# CM_ALIM.net
KiCad netlist of a schematic drawn in Altium Designer
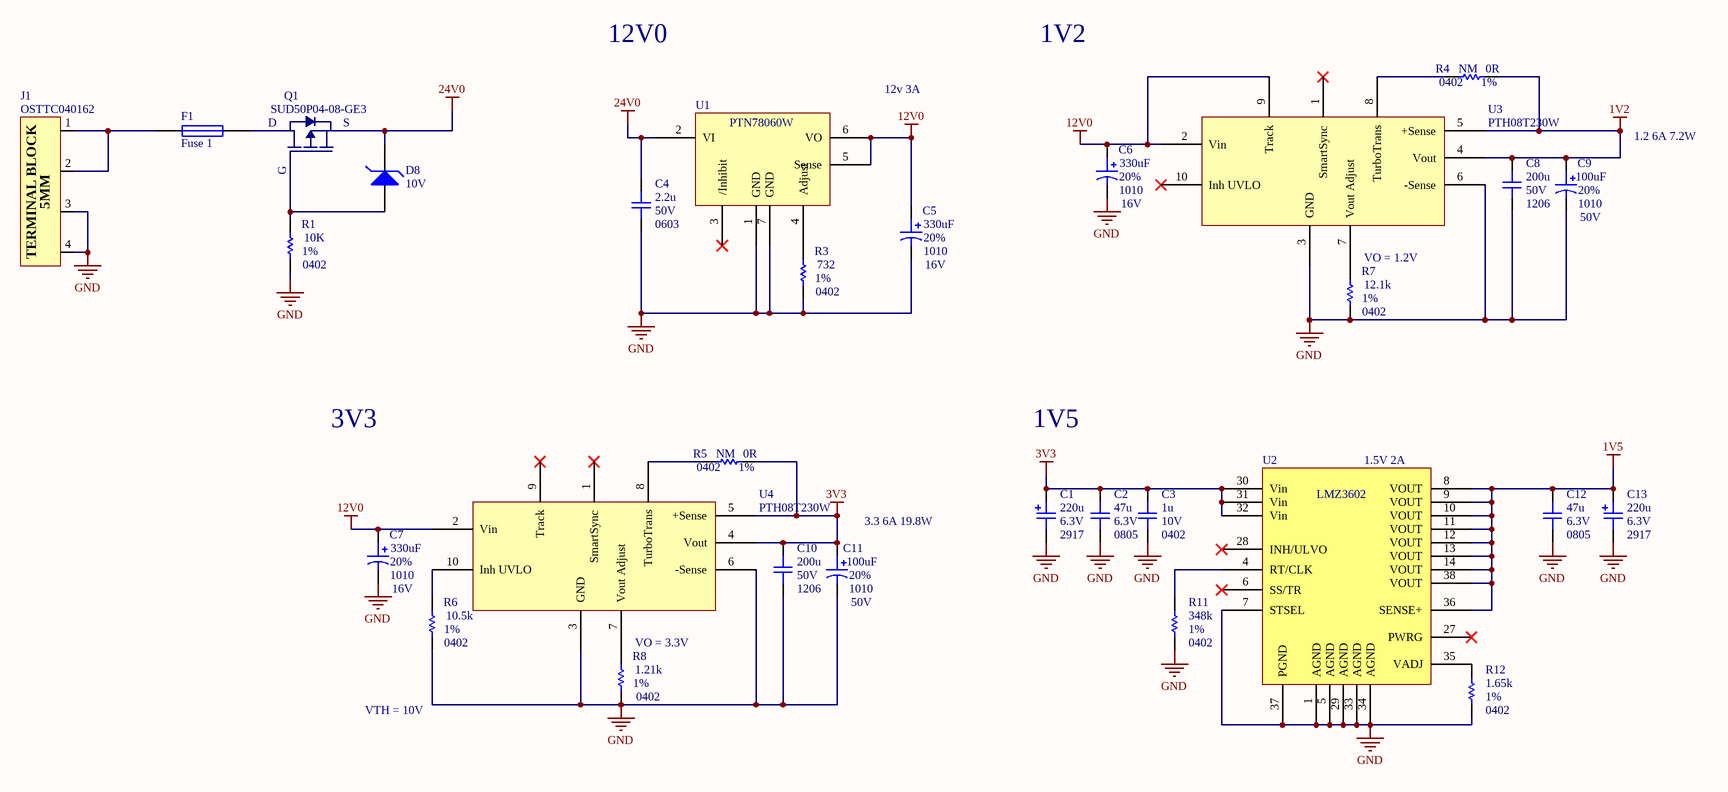
[diagram p0: CM_ALIM.SchDoc]

(export (version "E")
  (design (tool "Eeschema 10.0.6"))
  (components
    (comp (ref "C1")
      (value "220u")
      (footprint "CAP_TAN_2917(D)")
      (description "CAP - TANTALUM - 2917")
      (fields
        (field (name "VOLTAGE") "6.3V")
        (field (name "PACKAGE") "2917")
        (field (name "Comment") "CAP - TANTALUM - CASE D")
        (field (name "CREATEDBY") "Jonathan Bouchard")
      )
      (libsource (lib "S7CAS_Lib2019_REV1_00") (part "CAP_TANT_2917(D)"))
    )
    (comp (ref "C2")
      (value "47u")
      (footprint "CAP_0805")
      (description "CAP - 0805")
      (fields
        (field (name "VOLTAGE") "6.3V")
        (field (name "PACKAGE") "0805")
        (field (name "CREATEDBY") "Jonathan Bouchard")
      )
      (libsource (lib "S7CAS_Lib2019_REV1_00") (part "CAP - 0805"))
    )
    (comp (ref "C3")
      (value "1u")
      (footprint "CAP_0402")
      (description "CAP - 0402")
      (fields
        (field (name "VOLTAGE") "10V")
        (field (name "PACKAGE") "0402")
        (field (name "CREATEDBY") "Jonathan Bouchard")
      )
      (libsource (lib "S7CAS_Lib2019_REV1_00") (part "CAP - 0402"))
    )
    (comp (ref "C4")
      (value "2.2u")
      (footprint "CAP_0603")
      (description "CAP - 0603")
      (fields
        (field (name "VOLTAGE") "50V")
        (field (name "PACKAGE") "0603")
        (field (name "CREATEDBY") "Jonathan Bouchard")
      )
      (libsource (lib "S7CAS_Lib2019_REV1_00") (part "CAP - 0603"))
    )
    (comp (ref "C5")
      (value "330uF")
      (footprint "CAP_ALU_1010_vishay")
      (description "CAP - ALU 330uF 20% 16V - 1010")
      (fields
        (field (name "MFG") "Vishay Dale")
        (field (name "MFG PART NUMBER") "MAL214699501E3")
        (field (name "VOLTAGE") "16V")
        (field (name "PACKAGE") "1010")
        (field (name "PRECISION") "20%")
        (field (name "CREATEDBY") "Jonathan Bouchard")
      )
      (libsource (lib "S7CAS_Lib2019_REV1_00") (part "CAP_ALU_MAL214699501E3"))
    )
    (comp (ref "C6")
      (value "330uF")
      (footprint "CAP_ALU_1010_vishay")
      (description "CAP - ALU 330uF 20% 16V - 1010")
      (fields
        (field (name "MFG") "Vishay Dale")
        (field (name "MFG PART NUMBER") "MAL214699501E3")
        (field (name "VOLTAGE") "16V")
        (field (name "PACKAGE") "1010")
        (field (name "PRECISION") "20%")
        (field (name "CREATEDBY") "Jonathan Bouchard")
      )
      (libsource (lib "S7CAS_Lib2019_REV1_00") (part "CAP_ALU_MAL214699501E3"))
    )
    (comp (ref "C7")
      (value "330uF")
      (footprint "CAP_ALU_1010_vishay")
      (description "CAP - ALU 330uF 20% 16V - 1010")
      (fields
        (field (name "MFG") "Vishay Dale")
        (field (name "MFG PART NUMBER") "MAL214699501E3")
        (field (name "VOLTAGE") "16V")
        (field (name "PACKAGE") "1010")
        (field (name "PRECISION") "20%")
        (field (name "CREATEDBY") "Jonathan Bouchard")
      )
      (libsource (lib "S7CAS_Lib2019_REV1_00") (part "CAP_ALU_MAL214699501E3"))
    )
    (comp (ref "C8")
      (value "200u")
      (footprint "CAP_1206")
      (description "CAP - 1206")
      (fields
        (field (name "VOLTAGE") "50V")
        (field (name "PACKAGE") "1206")
        (field (name "CREATEDBY") "Jonathan Bouchard")
      )
      (libsource (lib "S7CAS_Lib2019_REV1_00") (part "CAP - 1206"))
    )
    (comp (ref "C9")
      (value "100uF")
      (footprint "CAP_ALU_1010_vishay")
      (description "CAP - ALU 100uF 20% 50V - 1010")
      (fields
        (field (name "MFG") "Vishay Dale")
        (field (name "MFG PART NUMBER") "MAL215099101E3")
        (field (name "VOLTAGE") "50V")
        (field (name "PACKAGE") "1010")
        (field (name "PRECISION") "20%")
        (field (name "CREATEDBY") "Jonathan Bouchard")
      )
      (libsource (lib "S7CAS_Lib2019_REV1_00") (part "CAP_ALU_MAL215099101E3"))
    )
    (comp (ref "C10")
      (value "200u")
      (footprint "CAP_1206")
      (description "CAP - 1206")
      (fields
        (field (name "VOLTAGE") "50V")
        (field (name "PACKAGE") "1206")
        (field (name "CREATEDBY") "Jonathan Bouchard")
      )
      (libsource (lib "S7CAS_Lib2019_REV1_00") (part "CAP - 1206"))
    )
    (comp (ref "C11")
      (value "100uF")
      (footprint "CAP_ALU_1010_vishay")
      (description "CAP - ALU 100uF 20% 50V - 1010")
      (fields
        (field (name "MFG") "Vishay Dale")
        (field (name "MFG PART NUMBER") "MAL215099101E3")
        (field (name "VOLTAGE") "50V")
        (field (name "PACKAGE") "1010")
        (field (name "PRECISION") "20%")
        (field (name "CREATEDBY") "Jonathan Bouchard")
      )
      (libsource (lib "S7CAS_Lib2019_REV1_00") (part "CAP_ALU_MAL215099101E3"))
    )
    (comp (ref "C12")
      (value "47u")
      (footprint "CAP_0805")
      (description "CAP - 0805")
      (fields
        (field (name "VOLTAGE") "6.3V")
        (field (name "PACKAGE") "0805")
        (field (name "CREATEDBY") "Jonathan Bouchard")
      )
      (libsource (lib "S7CAS_Lib2019_REV1_00") (part "CAP - 0805"))
    )
    (comp (ref "C13")
      (value "220u")
      (footprint "CAP_TAN_2917(D)")
      (description "CAP - TANTALUM - 2917")
      (fields
        (field (name "VOLTAGE") "6.3V")
        (field (name "PACKAGE") "2917")
        (field (name "Comment") "CAP - TANTALUM - CASE D")
        (field (name "CREATEDBY") "Jonathan Bouchard")
      )
      (libsource (lib "S7CAS_Lib2019_REV1_00") (part "CAP_TANT_2917(D)"))
    )
    (comp (ref "D8")
      (value "ZENER BZX84C10LT1G")
      (footprint "SOT23_N")
      (description "Zener Diode")
      (fields (field (name "VZ") "10V"))
      (libsource (lib "Custom") (part "ZENER BZX84C10LT1G"))
    )
    (comp (ref "F1")
      (value "Fuse 1")
      (footprint "PIN-W2/E2.8")
      (description "Fuse")
      (fields (field (name "PUBLISHER") "Altium Limited"))
      (libsource (lib "Miscellaneous Devices") (part "Fuse 1"))
    )
    (comp (ref "J1")
      (value "OSTTC040162")
      (footprint "CONN_TERMINAL_OSTTA040161")
      (description "CONN -  TERMINAL BLOCK 4POS 5MM - TH")
      (fields (field (name "MFG") "On Shore Technology Inc.") (field (name "CREATEDBY") "Jonathan Bouchard"))
      (libsource (lib "S7CAS_Lib2019_REV1_00") (part "CONN_TERMINAL_OSTTC040162"))
    )
    (comp (ref "Q1")
      (value "SUD50P04-08-GE3")
      (footprint "TO-252")
      (libsource (lib "Custom") (part "P-MOS SUD50P04-08-GE3"))
    )
    (comp (ref "R1")
      (value "10K")
      (footprint "RES_0402")
      (description "RES - 0402")
      (fields
        (field (name "VOLTAGE") "50V")
        (field (name "POWER") "1/16W")
        (field (name "PACKAGE") "0402")
        (field (name "PRECISION") "1%")
        (field (name "CREATEDBY") "Jonathan Bouchard")
      )
      (libsource (lib "S7CAS_Lib2019_REV1_00") (part "RES - 0402"))
    )
    (comp (ref "R3")
      (value "732")
      (footprint "RES_0402")
      (description "RES - 0402")
      (fields
        (field (name "VOLTAGE") "50V")
        (field (name "POWER") "1/16W")
        (field (name "PACKAGE") "0402")
        (field (name "PRECISION") "1%")
        (field (name "CREATEDBY") "Jonathan Bouchard")
      )
      (libsource (lib "S7CAS_Lib2019_REV1_00") (part "RES - 0402"))
    )
    (comp (ref "R4")
      (value "NM")
      (footprint "RES_0402")
      (description "RES - 0402")
      (fields
        (field (name "VOLTAGE") "50V")
        (field (name "POWER") "1/16W")
        (field (name "PACKAGE") "0402")
        (field (name "PRECISION") "1%")
        (field (name "ALTIUM_VALUE") "0R")
        (field (name "CREATEDBY") "Jonathan Bouchard")
      )
      (libsource (lib "S7CAS_Lib2019_REV1_00") (part "RES - 0402"))
    )
    (comp (ref "R5")
      (value "NM")
      (footprint "RES_0402")
      (description "RES - 0402")
      (fields
        (field (name "VOLTAGE") "50V")
        (field (name "POWER") "1/16W")
        (field (name "PACKAGE") "0402")
        (field (name "PRECISION") "1%")
        (field (name "ALTIUM_VALUE") "0R")
        (field (name "CREATEDBY") "Jonathan Bouchard")
      )
      (libsource (lib "S7CAS_Lib2019_REV1_00") (part "RES - 0402"))
    )
    (comp (ref "R6")
      (value "10.5k")
      (footprint "RES_0402")
      (description "RES - 0402")
      (fields
        (field (name "VOLTAGE") "50V")
        (field (name "POWER") "1/16W")
        (field (name "PACKAGE") "0402")
        (field (name "PRECISION") "1%")
        (field (name "CREATEDBY") "Jonathan Bouchard")
      )
      (libsource (lib "S7CAS_Lib2019_REV1_00") (part "RES - 0402"))
    )
    (comp (ref "R7")
      (value "12.1k")
      (footprint "RES_0402")
      (description "RES - 0402")
      (fields
        (field (name "VOLTAGE") "50V")
        (field (name "POWER") "1/16W")
        (field (name "PACKAGE") "0402")
        (field (name "PRECISION") "1%")
        (field (name "CREATEDBY") "Jonathan Bouchard")
      )
      (libsource (lib "S7CAS_Lib2019_REV1_00") (part "RES - 0402"))
    )
    (comp (ref "R8")
      (value "1.21k")
      (footprint "RES_0402")
      (description "RES - 0402")
      (fields
        (field (name "VOLTAGE") "50V")
        (field (name "POWER") "1/16W")
        (field (name "PACKAGE") "0402")
        (field (name "PRECISION") "1%")
        (field (name "CREATEDBY") "Jonathan Bouchard")
      )
      (libsource (lib "S7CAS_Lib2019_REV1_00") (part "RES - 0402"))
    )
    (comp (ref "R11")
      (value "348k")
      (footprint "RES_0402")
      (description "RES - 0402")
      (fields
        (field (name "VOLTAGE") "50V")
        (field (name "POWER") "1/16W")
        (field (name "PACKAGE") "0402")
        (field (name "PRECISION") "1%")
        (field (name "CREATEDBY") "Jonathan Bouchard")
      )
      (libsource (lib "S7CAS_Lib2019_REV1_00") (part "RES - 0402"))
    )
    (comp (ref "R12")
      (value "1.65k")
      (footprint "RES_0402")
      (description "RES - 0402")
      (fields
        (field (name "VOLTAGE") "50V")
        (field (name "POWER") "1/16W")
        (field (name "PACKAGE") "0402")
        (field (name "PRECISION") "1%")
        (field (name "CREATEDBY") "Jonathan Bouchard")
      )
      (libsource (lib "S7CAS_Lib2019_REV1_00") (part "RES - 0402"))
    )
    (comp (ref "U1")
      (value "PTN78060W")
      (footprint "EUW")
      (description "Wide input volate regulator")
      (libsource (lib "Custom") (part "PTN78060W"))
    )
    (comp (ref "U2")
      (value "LMZ3602")
      (footprint "RKG39 QFN")
      (description "2A Power Module")
      (libsource (lib "Custom") (part "LMZ3602"))
    )
    (comp (ref "U3")
      (value "PTH08T230W")
      (footprint "PTH08T230W")
      (libsource (lib "PTH08T230W") (part "PTH08T230W"))
    )
    (comp (ref "U4")
      (value "PTH08T230W")
      (footprint "PTH08T230W")
      (libsource (lib "PTH08T230W") (part "PTH08T230W"))
    )
  )
  (nets
    (net (code "1") (name "1V2") (class "Default")
      (node (ref "C8") (pin "2") (pinfunction "2_2") (pintype "passive"))
      (node (ref "C9") (pin "1") (pinfunction "1_1") (pintype "passive"))
      (node (ref "R4") (pin "1") (pinfunction "1_1") (pintype "passive"))
      (node (ref "U3") (pin "4") (pinfunction "Vout_4") (pintype "passive"))
      (node (ref "U3") (pin "5") (pinfunction "+Sense_5") (pintype "passive"))
    )
    (net (code "2") (name "1V5") (class "Default")
      (node (ref "C12") (pin "2") (pinfunction "2_2") (pintype "passive"))
      (node (ref "C13") (pin "2") (pinfunction "2_2") (pintype "passive"))
      (node (ref "U2") (pin "10") (pinfunction "VOUT_10") (pintype "passive"))
      (node (ref "U2") (pin "11") (pinfunction "VOUT_11") (pintype "passive"))
      (node (ref "U2") (pin "12") (pinfunction "VOUT_12") (pintype "passive"))
      (node (ref "U2") (pin "13") (pinfunction "VOUT_13") (pintype "passive"))
      (node (ref "U2") (pin "14") (pinfunction "VOUT_14") (pintype "passive"))
      (node (ref "U2") (pin "36") (pinfunction "SENSE+_36") (pintype "passive"))
      (node (ref "U2") (pin "38") (pinfunction "VOUT_38") (pintype "passive"))
      (node (ref "U2") (pin "8") (pinfunction "VOUT_8") (pintype "passive"))
      (node (ref "U2") (pin "9") (pinfunction "VOUT_9") (pintype "passive"))
    )
    (net (code "3") (name "3V3") (class "Default")
      (node (ref "C1") (pin "2") (pinfunction "2_2") (pintype "passive"))
      (node (ref "C10") (pin "2") (pinfunction "2_2") (pintype "passive"))
      (node (ref "C11") (pin "1") (pinfunction "1_1") (pintype "passive"))
      (node (ref "C2") (pin "2") (pinfunction "2_2") (pintype "passive"))
      (node (ref "C3") (pin "2") (pinfunction "2_2") (pintype "passive"))
      (node (ref "R5") (pin "1") (pinfunction "1_1") (pintype "passive"))
      (node (ref "U2") (pin "30") (pinfunction "Vin_30") (pintype "passive"))
      (node (ref "U2") (pin "31") (pinfunction "Vin_31") (pintype "passive"))
      (node (ref "U2") (pin "32") (pinfunction "Vin_32") (pintype "passive"))
      (node (ref "U4") (pin "4") (pinfunction "Vout_4") (pintype "passive"))
      (node (ref "U4") (pin "5") (pinfunction "+Sense_5") (pintype "passive"))
    )
    (net (code "4") (name "12V0") (class "Default")
      (node (ref "C5") (pin "1") (pinfunction "1_1") (pintype "passive"))
      (node (ref "C6") (pin "1") (pinfunction "1_1") (pintype "passive"))
      (node (ref "C7") (pin "1") (pinfunction "1_1") (pintype "passive"))
      (node (ref "U1") (pin "5") (pinfunction "Sense_5") (pintype "passive"))
      (node (ref "U1") (pin "6") (pinfunction "VO_6") (pintype "passive"))
      (node (ref "U3") (pin "2") (pinfunction "Vin_2") (pintype "passive"))
      (node (ref "U3") (pin "9") (pinfunction "Track_9") (pintype "passive"))
      (node (ref "U4") (pin "2") (pinfunction "Vin_2") (pintype "passive"))
    )
    (net (code "5") (name "24V0") (class "Default")
      (node (ref "C4") (pin "2") (pinfunction "2_2") (pintype "passive"))
      (node (ref "D8") (pin "3") (pinfunction "K_3") (pintype "passive"))
      (node (ref "Q1") (pin "S") (pinfunction "*_S") (pintype "passive"))
      (node (ref "U1") (pin "2") (pinfunction "VI_2") (pintype "passive"))
    )
    (net (code "6") (name "GND") (class "Default")
      (node (ref "C1") (pin "1") (pinfunction "1_1") (pintype "passive"))
      (node (ref "C10") (pin "1") (pinfunction "1_1") (pintype "passive"))
      (node (ref "C11") (pin "2") (pinfunction "2_2") (pintype "passive"))
      (node (ref "C12") (pin "1") (pinfunction "1_1") (pintype "passive"))
      (node (ref "C13") (pin "1") (pinfunction "1_1") (pintype "passive"))
      (node (ref "C2") (pin "1") (pinfunction "1_1") (pintype "passive"))
      (node (ref "C3") (pin "1") (pinfunction "1_1") (pintype "passive"))
      (node (ref "C4") (pin "1") (pinfunction "1_1") (pintype "passive"))
      (node (ref "C5") (pin "2") (pinfunction "2_2") (pintype "passive"))
      (node (ref "C6") (pin "2") (pinfunction "2_2") (pintype "passive"))
      (node (ref "C7") (pin "2") (pinfunction "2_2") (pintype "passive"))
      (node (ref "C8") (pin "1") (pinfunction "1_1") (pintype "passive"))
      (node (ref "C9") (pin "2") (pinfunction "2_2") (pintype "passive"))
      (node (ref "J1") (pin "3") (pinfunction "3_3") (pintype "passive"))
      (node (ref "J1") (pin "4") (pinfunction "4_4") (pintype "passive"))
      (node (ref "R1") (pin "1") (pinfunction "1_1") (pintype "passive"))
      (node (ref "R11") (pin "1") (pinfunction "1_1") (pintype "passive"))
      (node (ref "R12") (pin "1") (pinfunction "1_1") (pintype "passive"))
      (node (ref "R3") (pin "1") (pinfunction "1_1") (pintype "passive"))
      (node (ref "R6") (pin "1") (pinfunction "1_1") (pintype "passive"))
      (node (ref "R7") (pin "1") (pinfunction "1_1") (pintype "passive"))
      (node (ref "R8") (pin "1") (pinfunction "1_1") (pintype "passive"))
      (node (ref "U1") (pin "1") (pinfunction "GND_1") (pintype "passive"))
      (node (ref "U1") (pin "7") (pinfunction "GND_7") (pintype "passive"))
      (node (ref "U2") (pin "1") (pinfunction "AGND_1") (pintype "passive"))
      (node (ref "U2") (pin "29") (pinfunction "AGND_29") (pintype "passive"))
      (node (ref "U2") (pin "33") (pinfunction "AGND_33") (pintype "passive"))
      (node (ref "U2") (pin "34") (pinfunction "AGND_34") (pintype "passive"))
      (node (ref "U2") (pin "37") (pinfunction "PGND_37") (pintype "passive"))
      (node (ref "U2") (pin "5") (pinfunction "AGND_5") (pintype "passive"))
      (node (ref "U2") (pin "7") (pinfunction "STSEL_7") (pintype "passive"))
      (node (ref "U3") (pin "3") (pinfunction "GND_3") (pintype "passive"))
      (node (ref "U3") (pin "6") (pinfunction "-Sense_6") (pintype "passive"))
      (node (ref "U4") (pin "3") (pinfunction "GND_3") (pintype "passive"))
      (node (ref "U4") (pin "6") (pinfunction "-Sense_6") (pintype "passive"))
    )
    (net (code "7") (name "Net-(D8-A)") (class "Default")
      (node (ref "D8") (pin "1") (pinfunction "A_1") (pintype "passive"))
      (node (ref "Q1") (pin "G") (pinfunction "*_G") (pintype "passive"))
      (node (ref "R1") (pin "2") (pinfunction "2_2") (pintype "passive"))
    )
    (net (code "8") (name "Net-(F1-Pad1)") (class "Default")
      (node (ref "F1") (pin "1") (pinfunction "1_1") (pintype "passive"))
      (node (ref "J1") (pin "1") (pinfunction "1_1") (pintype "passive"))
      (node (ref "J1") (pin "2") (pinfunction "2_2") (pintype "passive"))
    )
    (net (code "9") (name "Net-(F1-Pad2)") (class "Default")
      (node (ref "F1") (pin "2") (pinfunction "2_2") (pintype "passive"))
      (node (ref "Q1") (pin "D") (pinfunction "*_D") (pintype "passive"))
    )
    (net (code "10") (name "Net-(U1-Adjust)") (class "Default")
      (node (ref "R3") (pin "2") (pinfunction "2_2") (pintype "passive"))
      (node (ref "U1") (pin "4") (pinfunction "Adjust_4") (pintype "passive"))
    )
    (net (code "11") (name "Net-(U2-RT{slash}CLK)") (class "Default")
      (node (ref "R11") (pin "2") (pinfunction "2_2") (pintype "passive"))
      (node (ref "U2") (pin "4") (pinfunction "RT/CLK_4") (pintype "passive"))
    )
    (net (code "12") (name "Net-(U2-VADJ)") (class "Default")
      (node (ref "R12") (pin "2") (pinfunction "2_2") (pintype "passive"))
      (node (ref "U2") (pin "35") (pinfunction "VADJ_35") (pintype "passive"))
    )
    (net (code "13") (name "Net-(U3-TurboTrans)") (class "Default")
      (node (ref "R4") (pin "2") (pinfunction "2_2") (pintype "passive"))
      (node (ref "U3") (pin "8") (pinfunction "TurboTrans_8") (pintype "passive"))
    )
    (net (code "14") (name "Net-(U3-Vout_Adjust)") (class "Default")
      (node (ref "R7") (pin "2") (pinfunction "2_2") (pintype "passive"))
      (node (ref "U3") (pin "7") (pinfunction "Vout_Adjust_7") (pintype "passive"))
    )
    (net (code "15") (name "Net-(U4-Inh_UVLO)") (class "Default")
      (node (ref "R6") (pin "2") (pinfunction "2_2") (pintype "passive"))
      (node (ref "U4") (pin "10") (pinfunction "Inh_UVLO_10") (pintype "passive"))
    )
    (net (code "16") (name "Net-(U4-TurboTrans)") (class "Default")
      (node (ref "R5") (pin "2") (pinfunction "2_2") (pintype "passive"))
      (node (ref "U4") (pin "8") (pinfunction "TurboTrans_8") (pintype "passive"))
    )
    (net (code "17") (name "Net-(U4-Vout_Adjust)") (class "Default")
      (node (ref "R8") (pin "2") (pinfunction "2_2") (pintype "passive"))
      (node (ref "U4") (pin "7") (pinfunction "Vout_Adjust_7") (pintype "passive"))
    )
    (net (code "18") (name "unconnected-(U1-{slash}Inhibit-Pad3)") (class "Default")
      (node (ref "U1") (pin "3") (pinfunction "/Inhibit_3") (pintype "passive+no_connect"))
    )
    (net (code "19") (name "unconnected-(U2-INH{slash}ULVO-Pad28)") (class "Default")
      (node (ref "U2") (pin "28") (pinfunction "INH/ULVO_28") (pintype "passive+no_connect"))
    )
    (net (code "20") (name "unconnected-(U2-PWRG-Pad27)") (class "Default")
      (node (ref "U2") (pin "27") (pinfunction "PWRG_27") (pintype "passive+no_connect"))
    )
    (net (code "21") (name "unconnected-(U2-SS{slash}TR-Pad6)") (class "Default")
      (node (ref "U2") (pin "6") (pinfunction "SS/TR_6") (pintype "passive+no_connect"))
    )
    (net (code "22") (name "unconnected-(U3-Inh_UVLO-Pad10)") (class "Default")
      (node (ref "U3") (pin "10") (pinfunction "Inh_UVLO_10") (pintype "passive+no_connect"))
    )
    (net (code "23") (name "unconnected-(U3-SmartSync-Pad1)") (class "Default")
      (node (ref "U3") (pin "1") (pinfunction "SmartSync_1") (pintype "passive+no_connect"))
    )
    (net (code "24") (name "unconnected-(U4-SmartSync-Pad1)") (class "Default")
      (node (ref "U4") (pin "1") (pinfunction "SmartSync_1") (pintype "passive+no_connect"))
    )
    (net (code "25") (name "unconnected-(U4-Track-Pad9)") (class "Default")
      (node (ref "U4") (pin "9") (pinfunction "Track_9") (pintype "passive+no_connect"))
    )
  )
)
